# rpi_shield.net
KiCad netlist of a schematic drawn in Altium Designer
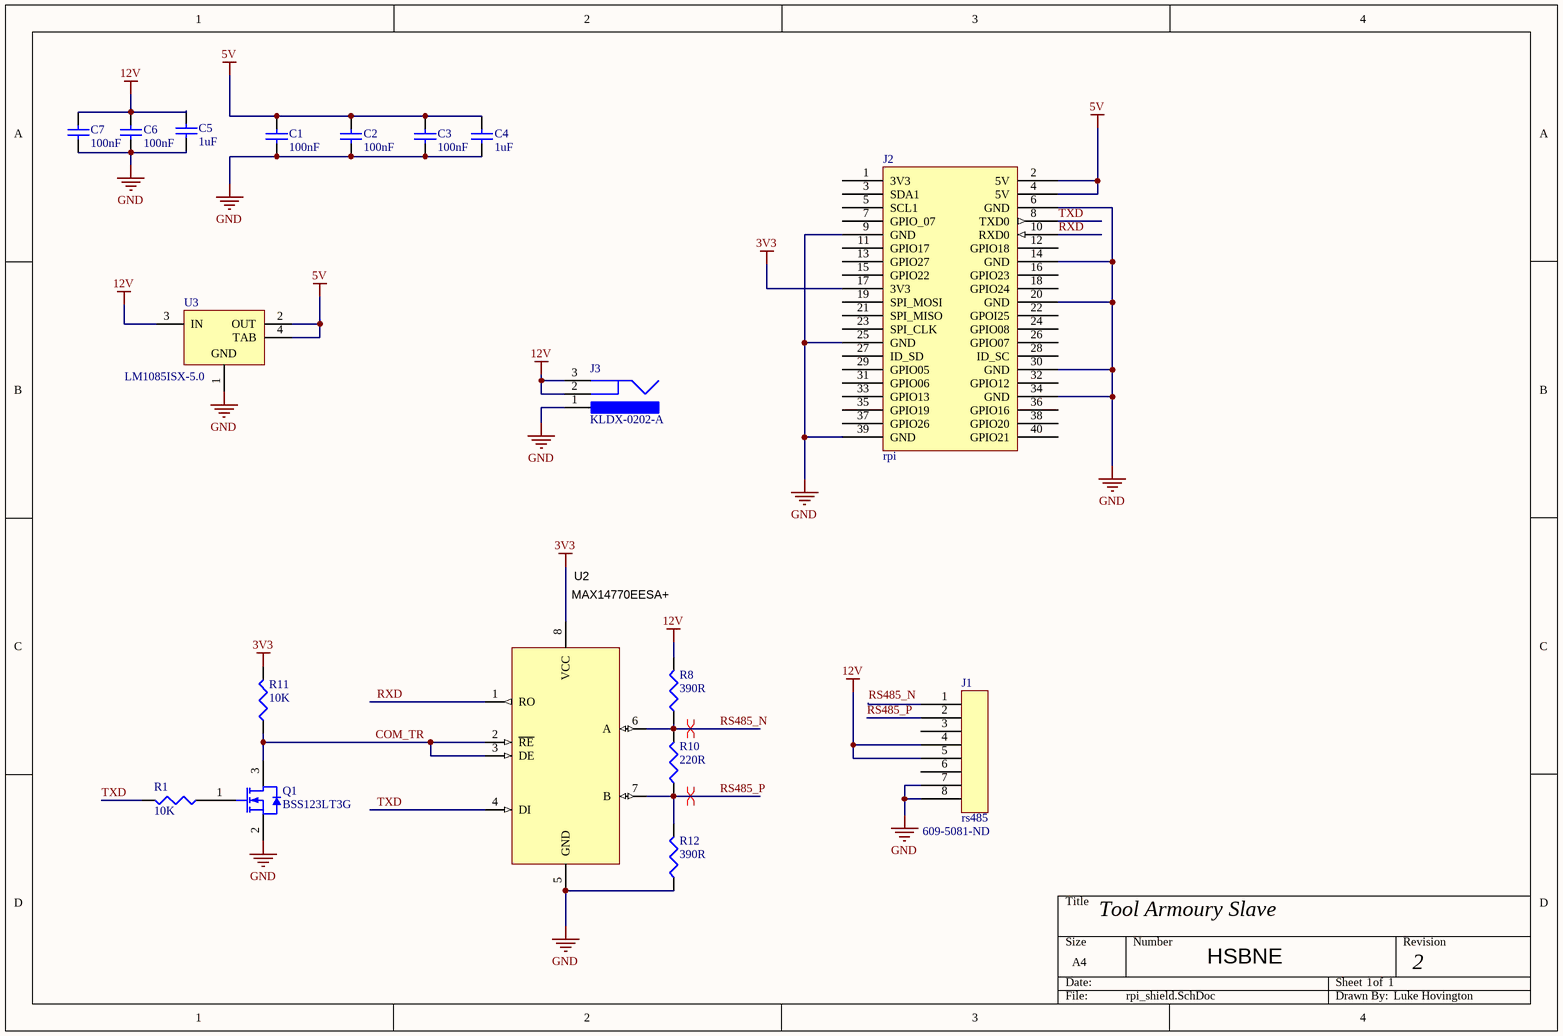
[diagram p0: rpi_shield.SchDoc]

(export (version "E")
  (design (tool "Eeschema 10.0.6"))
  (components
    (comp (ref "C1")
      (value "100nF")
      (footprint "C1206")
      (description "Capacitor (Semiconductor SIM Model)")
      (fields (field (name "PUBLISHER") "Altium Limited"))
      (libsource (lib "ToolDoorController") (part "Cap 100nF"))
    )
    (comp (ref "C2")
      (value "100nF")
      (footprint "C1206")
      (description "Capacitor (Semiconductor SIM Model)")
      (fields (field (name "PUBLISHER") "Altium Limited"))
      (libsource (lib "ToolDoorController") (part "Cap 100nF"))
    )
    (comp (ref "C3")
      (value "100nF")
      (footprint "C1206")
      (description "Capacitor (Semiconductor SIM Model)")
      (fields (field (name "PUBLISHER") "Altium Limited"))
      (libsource (lib "ToolDoorController") (part "Cap 100nF"))
    )
    (comp (ref "C4")
      (value "1uF")
      (footprint "C1206")
      (description "Capacitor (Semiconductor SIM Model)")
      (fields (field (name "PUBLISHER") "Altium Limited"))
      (libsource (lib "ToolDoorController") (part "Cap 1uF"))
    )
    (comp (ref "C5")
      (value "1uF")
      (footprint "C1206")
      (description "Capacitor (Semiconductor SIM Model)")
      (fields (field (name "PUBLISHER") "Altium Limited"))
      (libsource (lib "ToolDoorController") (part "Cap 1uF"))
    )
    (comp (ref "C6")
      (value "100nF")
      (footprint "C1206")
      (description "Capacitor (Semiconductor SIM Model)")
      (fields (field (name "PUBLISHER") "Altium Limited"))
      (libsource (lib "ToolDoorController") (part "Cap 100nF"))
    )
    (comp (ref "C7")
      (value "100nF")
      (footprint "C1206")
      (description "Capacitor (Semiconductor SIM Model)")
      (fields (field (name "PUBLISHER") "Altium Limited"))
      (libsource (lib "ToolDoorController") (part "Cap 100nF"))
    )
    (comp (ref "J1")
      (value "rs485")
      (footprint "RJ45")
      (description "rj45")
      (fields (field (name "SUPPLIER PART NUMBER 1") "609-5081-ND"))
      (libsource (lib "ToolDoorController") (part "rj45"))
    )
    (comp (ref "J2")
      (value "rpi")
      (footprint "2x20")
      (description "RaspPi I/O header")
      (libsource (lib "rpi_shield") (part "rpi2"))
    )
    (comp (ref "J3")
      (value "KLDX-0202-A")
      (footprint "KYCN-KLDX-0202-A_V")
      (description "DC Power Jack, 24 V, 3.5 A, -25 to 85 degC, 3-Pin THD, RoHS")
      (fields (field (name "MANUFACTURER") "Kycon"))
      (libsource (lib "Altium Content Vault") (part "JACK-2CD3-RN"))
    )
    (comp (ref "Q1")
      (value "BSS123LT3G")
      (footprint "ONSC-SOT-23-3-318-08_V")
      (description "Power MOSFET, 170 mA, 100 V, N-Channel, 3-Pin SOT-23, Pb-Free, Tape and Reel")
      (fields (field (name "MANUFACTURER") "On Semiconductor"))
      (libsource (lib "Altium Content Vault") (part "ONSC-NMOS-G1S2D3-3"))
    )
    (comp (ref "R1")
      (value "10K")
      (footprint "C1206")
      (description "Resistor-10K")
      (fields (field (name "PUBLISHER") "Altium Limited"))
      (libsource (lib "ToolDoorController") (part "Resistor-10K"))
    )
    (comp (ref "R8")
      (value "390R")
      (footprint "C1206")
      (description "Resistor-390R")
      (fields (field (name "PUBLISHER") "Altium Limited"))
      (libsource (lib "ToolDoorController") (part "Resistor-390R"))
    )
    (comp (ref "R10")
      (value "220R")
      (footprint "C1206")
      (description "Resistor-220R")
      (fields (field (name "PUBLISHER") "Altium Limited"))
      (libsource (lib "ToolDoorController") (part "Resistor-220R"))
    )
    (comp (ref "R11")
      (value "10K")
      (footprint "C1206")
      (description "Resistor-10K")
      (fields (field (name "PUBLISHER") "Altium Limited"))
      (libsource (lib "ToolDoorController") (part "Resistor-10K"))
    )
    (comp (ref "R12")
      (value "390R")
      (footprint "C1206")
      (description "Resistor-390R")
      (fields (field (name "PUBLISHER") "Altium Limited"))
      (libsource (lib "ToolDoorController") (part "Resistor-390R"))
    )
    (comp (ref "U2")
      (value "MAX14770EESA+")
      (footprint "8S1_L")
      (description "TXRX PROFIBUS RS-485 8-SOIC")
      (libsource (lib "ToolDoorController") (part "MAX14770EESA+"))
    )
    (comp (ref "U3")
      (value "LM1085ISX-5.0")
      (footprint "TS3B_L")
      (description "3A Low Dropout Positive Regulators, 3-pin TO-263")
      (fields (field (name "MANUFACTURER") "National Semiconductor"))
      (libsource (lib "Altium Content Vault") (part "PM-REG-LM1086-SOT4"))
    )
  )
  (nets
    (net (code "1") (name "/COM_TR") (class "Default")
      (node (ref "Q1") (pin "3") (pinfunction "D_3") (pintype "passive"))
      (node (ref "R11") (pin "1") (pinfunction "1_1") (pintype "passive"))
      (node (ref "U2") (pin "2") (pinfunction "~{RE}_2") (pintype "input"))
      (node (ref "U2") (pin "3") (pinfunction "DE_3") (pintype "input"))
    )
    (net (code "2") (name "/RS485_N") (class "Default")
      (node (ref "J1") (pin "1") (pinfunction "1_1") (pintype "power_in"))
      (node (ref "R10") (pin "2") (pinfunction "2_2") (pintype "passive"))
      (node (ref "R8") (pin "1") (pinfunction "1_1") (pintype "passive"))
      (node (ref "U2") (pin "6") (pinfunction "A_6") (pintype "bidirectional"))
    )
    (net (code "3") (name "/RS485_P") (class "Default")
      (node (ref "J1") (pin "2") (pinfunction "2_2") (pintype "power_in"))
      (node (ref "R10") (pin "1") (pinfunction "1_1") (pintype "passive"))
      (node (ref "R12") (pin "2") (pinfunction "2_2") (pintype "passive"))
      (node (ref "U2") (pin "7") (pinfunction "B_7") (pintype "bidirectional"))
    )
    (net (code "4") (name "/RXD") (class "Default")
      (node (ref "J2") (pin "10") (pinfunction "RXD0_10") (pintype "input"))
      (node (ref "U2") (pin "1") (pinfunction "RO_1") (pintype "output"))
    )
    (net (code "5") (name "/TXD") (class "Default")
      (node (ref "J2") (pin "8") (pinfunction "TXD0_8") (pintype "output"))
      (node (ref "R1") (pin "2") (pinfunction "2_2") (pintype "passive"))
      (node (ref "U2") (pin "4") (pinfunction "DI_4") (pintype "input"))
    )
    (net (code "6") (name "3V3") (class "Default")
      (node (ref "J2") (pin "17") (pinfunction "3V3_17") (pintype "power_in"))
      (node (ref "R11") (pin "2") (pinfunction "2_2") (pintype "passive"))
      (node (ref "U2") (pin "8") (pinfunction "VCC_8") (pintype "power_in"))
    )
    (net (code "7") (name "5V") (class "Default")
      (node (ref "C1") (pin "2") (pinfunction "2_2") (pintype "passive"))
      (node (ref "C2") (pin "2") (pinfunction "2_2") (pintype "passive"))
      (node (ref "C3") (pin "2") (pinfunction "2_2") (pintype "passive"))
      (node (ref "C4") (pin "2") (pinfunction "2_2") (pintype "passive"))
      (node (ref "J2") (pin "2") (pinfunction "5V_2") (pintype "power_in"))
      (node (ref "J2") (pin "4") (pinfunction "5V_4") (pintype "power_in"))
      (node (ref "U3") (pin "2") (pinfunction "OUT_2") (pintype "power_in"))
      (node (ref "U3") (pin "4") (pinfunction "TAB_4") (pintype "power_in"))
    )
    (net (code "8") (name "12V") (class "Default")
      (node (ref "C5") (pin "2") (pinfunction "2_2") (pintype "passive"))
      (node (ref "C6") (pin "2") (pinfunction "2_2") (pintype "passive"))
      (node (ref "C7") (pin "2") (pinfunction "2_2") (pintype "passive"))
      (node (ref "J1") (pin "4") (pinfunction "4_4") (pintype "power_in"))
      (node (ref "J1") (pin "5") (pinfunction "5_5") (pintype "power_in"))
      (node (ref "J3") (pin "2") (pinfunction "2_2") (pintype "passive"))
      (node (ref "J3") (pin "3") (pinfunction "3_3") (pintype "passive"))
      (node (ref "R8") (pin "2") (pinfunction "2_2") (pintype "passive"))
      (node (ref "U3") (pin "3") (pinfunction "IN_3") (pintype "power_in"))
    )
    (net (code "9") (name "GND") (class "Default")
      (node (ref "C1") (pin "1") (pinfunction "1_1") (pintype "passive"))
      (node (ref "C2") (pin "1") (pinfunction "1_1") (pintype "passive"))
      (node (ref "C3") (pin "1") (pinfunction "1_1") (pintype "passive"))
      (node (ref "C4") (pin "1") (pinfunction "1_1") (pintype "passive"))
      (node (ref "C5") (pin "1") (pinfunction "1_1") (pintype "passive"))
      (node (ref "C6") (pin "1") (pinfunction "1_1") (pintype "passive"))
      (node (ref "C7") (pin "1") (pinfunction "1_1") (pintype "passive"))
      (node (ref "J1") (pin "7") (pinfunction "7_7") (pintype "power_in"))
      (node (ref "J1") (pin "8") (pinfunction "8_8") (pintype "power_in"))
      (node (ref "J2") (pin "14") (pinfunction "GND_14") (pintype "power_in"))
      (node (ref "J2") (pin "20") (pinfunction "GND_20") (pintype "power_in"))
      (node (ref "J2") (pin "25") (pinfunction "GND_25") (pintype "power_in"))
      (node (ref "J2") (pin "30") (pinfunction "GND_30") (pintype "power_in"))
      (node (ref "J2") (pin "34") (pinfunction "GND_34") (pintype "power_in"))
      (node (ref "J2") (pin "39") (pinfunction "GND_39") (pintype "power_in"))
      (node (ref "J2") (pin "6") (pinfunction "GND_6") (pintype "power_in"))
      (node (ref "J2") (pin "9") (pinfunction "GND_9") (pintype "power_in"))
      (node (ref "J3") (pin "1") (pinfunction "1_1") (pintype "passive"))
      (node (ref "Q1") (pin "2") (pinfunction "S_2") (pintype "passive"))
      (node (ref "R12") (pin "1") (pinfunction "1_1") (pintype "passive"))
      (node (ref "U2") (pin "5") (pinfunction "GND_5") (pintype "power_in"))
      (node (ref "U3") (pin "1") (pinfunction "GND_1") (pintype "power_in"))
    )
    (net (code "10") (name "Net-(Q1-G)") (class "Default")
      (node (ref "Q1") (pin "1") (pinfunction "G_1") (pintype "passive"))
      (node (ref "R1") (pin "1") (pinfunction "1_1") (pintype "passive"))
    )
    (net (code "11") (name "unconnected-(J1-Pad3)") (class "Default")
      (node (ref "J1") (pin "3") (pinfunction "3_3") (pintype "power_in"))
    )
    (net (code "12") (name "unconnected-(J1-Pad6)") (class "Default")
      (node (ref "J1") (pin "6") (pinfunction "6_6") (pintype "power_in"))
    )
    (net (code "13") (name "unconnected-(J2-3V3-Pad1)") (class "Default")
      (node (ref "J2") (pin "1") (pinfunction "3V3_1") (pintype "power_in"))
    )
    (net (code "14") (name "unconnected-(J2-GPIO05-Pad29)") (class "Default")
      (node (ref "J2") (pin "29") (pinfunction "GPIO05_29") (pintype "power_in"))
    )
    (net (code "15") (name "unconnected-(J2-GPIO06-Pad31)") (class "Default")
      (node (ref "J2") (pin "31") (pinfunction "GPIO06_31") (pintype "power_in"))
    )
    (net (code "16") (name "unconnected-(J2-GPIO07-Pad26)") (class "Default")
      (node (ref "J2") (pin "26") (pinfunction "GPIO07_26") (pintype "power_in"))
    )
    (net (code "17") (name "unconnected-(J2-GPIO08-Pad24)") (class "Default")
      (node (ref "J2") (pin "24") (pinfunction "GPIO08_24") (pintype "power_in"))
    )
    (net (code "18") (name "unconnected-(J2-GPIO12-Pad32)") (class "Default")
      (node (ref "J2") (pin "32") (pinfunction "GPIO12_32") (pintype "power_in"))
    )
    (net (code "19") (name "unconnected-(J2-GPIO13-Pad33)") (class "Default")
      (node (ref "J2") (pin "33") (pinfunction "GPIO13_33") (pintype "power_in"))
    )
    (net (code "20") (name "unconnected-(J2-GPIO16-Pad36)") (class "Default")
      (node (ref "J2") (pin "36") (pinfunction "GPIO16_36") (pintype "power_in"))
    )
    (net (code "21") (name "unconnected-(J2-GPIO17-Pad11)") (class "Default")
      (node (ref "J2") (pin "11") (pinfunction "GPIO17_11") (pintype "power_in"))
    )
    (net (code "22") (name "unconnected-(J2-GPIO18-Pad12)") (class "Default")
      (node (ref "J2") (pin "12") (pinfunction "GPIO18_12") (pintype "power_in"))
    )
    (net (code "23") (name "unconnected-(J2-GPIO19-Pad35)") (class "Default")
      (node (ref "J2") (pin "35") (pinfunction "GPIO19_35") (pintype "power_in"))
    )
    (net (code "24") (name "unconnected-(J2-GPIO20-Pad38)") (class "Default")
      (node (ref "J2") (pin "38") (pinfunction "GPIO20_38") (pintype "power_in"))
    )
    (net (code "25") (name "unconnected-(J2-GPIO21-Pad40)") (class "Default")
      (node (ref "J2") (pin "40") (pinfunction "GPIO21_40") (pintype "power_in"))
    )
    (net (code "26") (name "unconnected-(J2-GPIO22-Pad15)") (class "Default")
      (node (ref "J2") (pin "15") (pinfunction "GPIO22_15") (pintype "power_in"))
    )
    (net (code "27") (name "unconnected-(J2-GPIO23-Pad16)") (class "Default")
      (node (ref "J2") (pin "16") (pinfunction "GPIO23_16") (pintype "power_in"))
    )
    (net (code "28") (name "unconnected-(J2-GPIO24-Pad18)") (class "Default")
      (node (ref "J2") (pin "18") (pinfunction "GPIO24_18") (pintype "power_in"))
    )
    (net (code "29") (name "unconnected-(J2-GPIO26-Pad37)") (class "Default")
      (node (ref "J2") (pin "37") (pinfunction "GPIO26_37") (pintype "power_in"))
    )
    (net (code "30") (name "unconnected-(J2-GPIO27-Pad13)") (class "Default")
      (node (ref "J2") (pin "13") (pinfunction "GPIO27_13") (pintype "power_in"))
    )
    (net (code "31") (name "unconnected-(J2-GPIO_07-Pad7)") (class "Default")
      (node (ref "J2") (pin "7") (pinfunction "GPIO_07_7") (pintype "power_in"))
    )
    (net (code "32") (name "unconnected-(J2-GPOI25-Pad22)") (class "Default")
      (node (ref "J2") (pin "22") (pinfunction "GPOI25_22") (pintype "power_in"))
    )
    (net (code "33") (name "unconnected-(J2-ID_SC-Pad28)") (class "Default")
      (node (ref "J2") (pin "28") (pinfunction "ID_SC_28") (pintype "power_in"))
    )
    (net (code "34") (name "unconnected-(J2-ID_SD-Pad27)") (class "Default")
      (node (ref "J2") (pin "27") (pinfunction "ID_SD_27") (pintype "power_in"))
    )
    (net (code "35") (name "unconnected-(J2-SCL1-Pad5)") (class "Default")
      (node (ref "J2") (pin "5") (pinfunction "SCL1_5") (pintype "power_in"))
    )
    (net (code "36") (name "unconnected-(J2-SDA1-Pad3)") (class "Default")
      (node (ref "J2") (pin "3") (pinfunction "SDA1_3") (pintype "power_in"))
    )
    (net (code "37") (name "unconnected-(J2-SPI_CLK-Pad23)") (class "Default")
      (node (ref "J2") (pin "23") (pinfunction "SPI_CLK_23") (pintype "power_in"))
    )
    (net (code "38") (name "unconnected-(J2-SPI_MISO-Pad21)") (class "Default")
      (node (ref "J2") (pin "21") (pinfunction "SPI_MISO_21") (pintype "power_in"))
    )
    (net (code "39") (name "unconnected-(J2-SPI_MOSI-Pad19)") (class "Default")
      (node (ref "J2") (pin "19") (pinfunction "SPI_MOSI_19") (pintype "power_in"))
    )
  )
)
